# QUTMS-TSAL-S00.net
KiCad netlist of a schematic drawn in Altium Designer
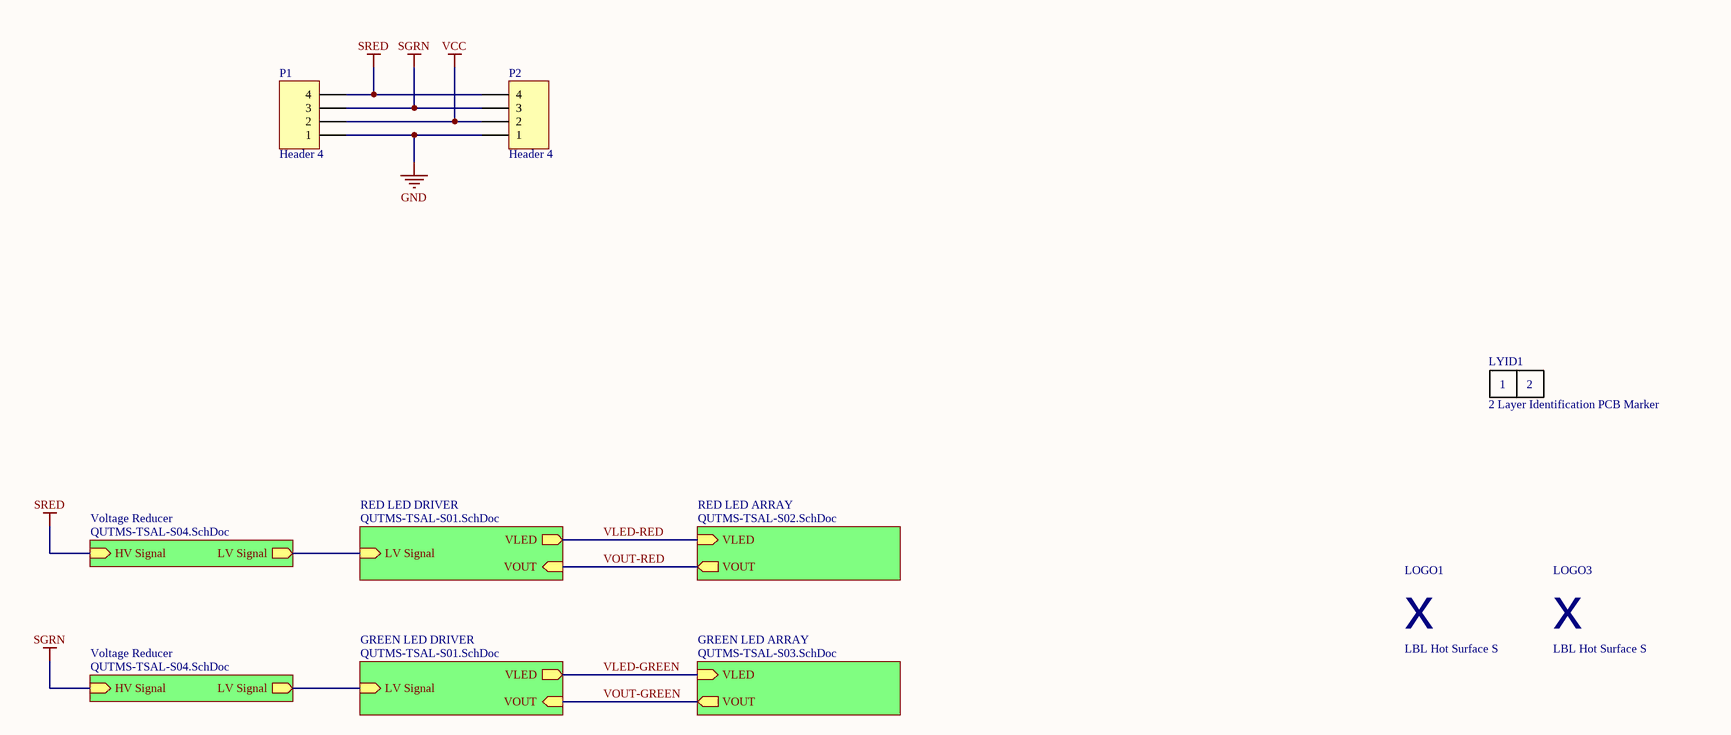
[diagram p0: QUTMS-TSAL-S00.SchDoc]

(export (version "E")
  (design (tool "Eeschema 10.0.6"))
  (components
    (comp (ref "LOGO1")
      (value "LBL Hot Surface S")
      (footprint "LBL HOT SMALL")
      (libsource (lib "QUTMS_PCBLibrary") (part "LBL Hot Surface S"))
    )
    (comp (ref "LOGO3")
      (value "LBL Hot Surface S")
      (footprint "LBL HOT SMALL")
      (libsource (lib "QUTMS_PCBLibrary") (part "LBL Hot Surface S"))
    )
    (comp (ref "LYID1")
      (value "2 Layer Identification PCB Marker")
      (footprint "LAYER IDENT 2")
      (libsource (lib "QUTMS_PCBLibrary") (part "Layer Identification 2"))
    )
    (comp (ref "P1")
      (value "Header 4")
      (footprint "HDR1X4")
      (description "Header, 4-Pin")
      (fields (field (name "PUBLISHER") "Altium Limited"))
      (libsource (lib "Miscellaneous Connectors") (part "Header 4"))
    )
    (comp (ref "P2")
      (value "Header 4")
      (footprint "HDR1X4")
      (description "Header, 4-Pin")
      (fields (field (name "PUBLISHER") "Altium Limited"))
      (libsource (lib "") (part "Header 4_1"))
    )
  )
  (nets
    (net (code "7") (name "GND") (class "Default")
      (node (ref "P1") (pin "1") (pinfunction "1_1") (pintype "passive"))
      (node (ref "P2") (pin "1") (pinfunction "1_1") (pintype "passive"))
    )
    (net (code "8") (name "SGRN") (class "Default")
      (node (ref "P1") (pin "3") (pinfunction "3_3") (pintype "passive"))
      (node (ref "P2") (pin "3") (pinfunction "3_3") (pintype "passive"))
    )
    (net (code "9") (name "SRED") (class "Default")
      (node (ref "P1") (pin "4") (pinfunction "4_4") (pintype "passive"))
      (node (ref "P2") (pin "4") (pinfunction "4_4") (pintype "passive"))
    )
    (net (code "10") (name "VCC") (class "Default")
      (node (ref "P1") (pin "2") (pinfunction "2_2") (pintype "passive"))
      (node (ref "P2") (pin "2") (pinfunction "2_2") (pintype "passive"))
    )
  )
)
